# PAPR_STM32F030F4_V2.net
KiCad netlist of a schematic drawn in EasyEDA
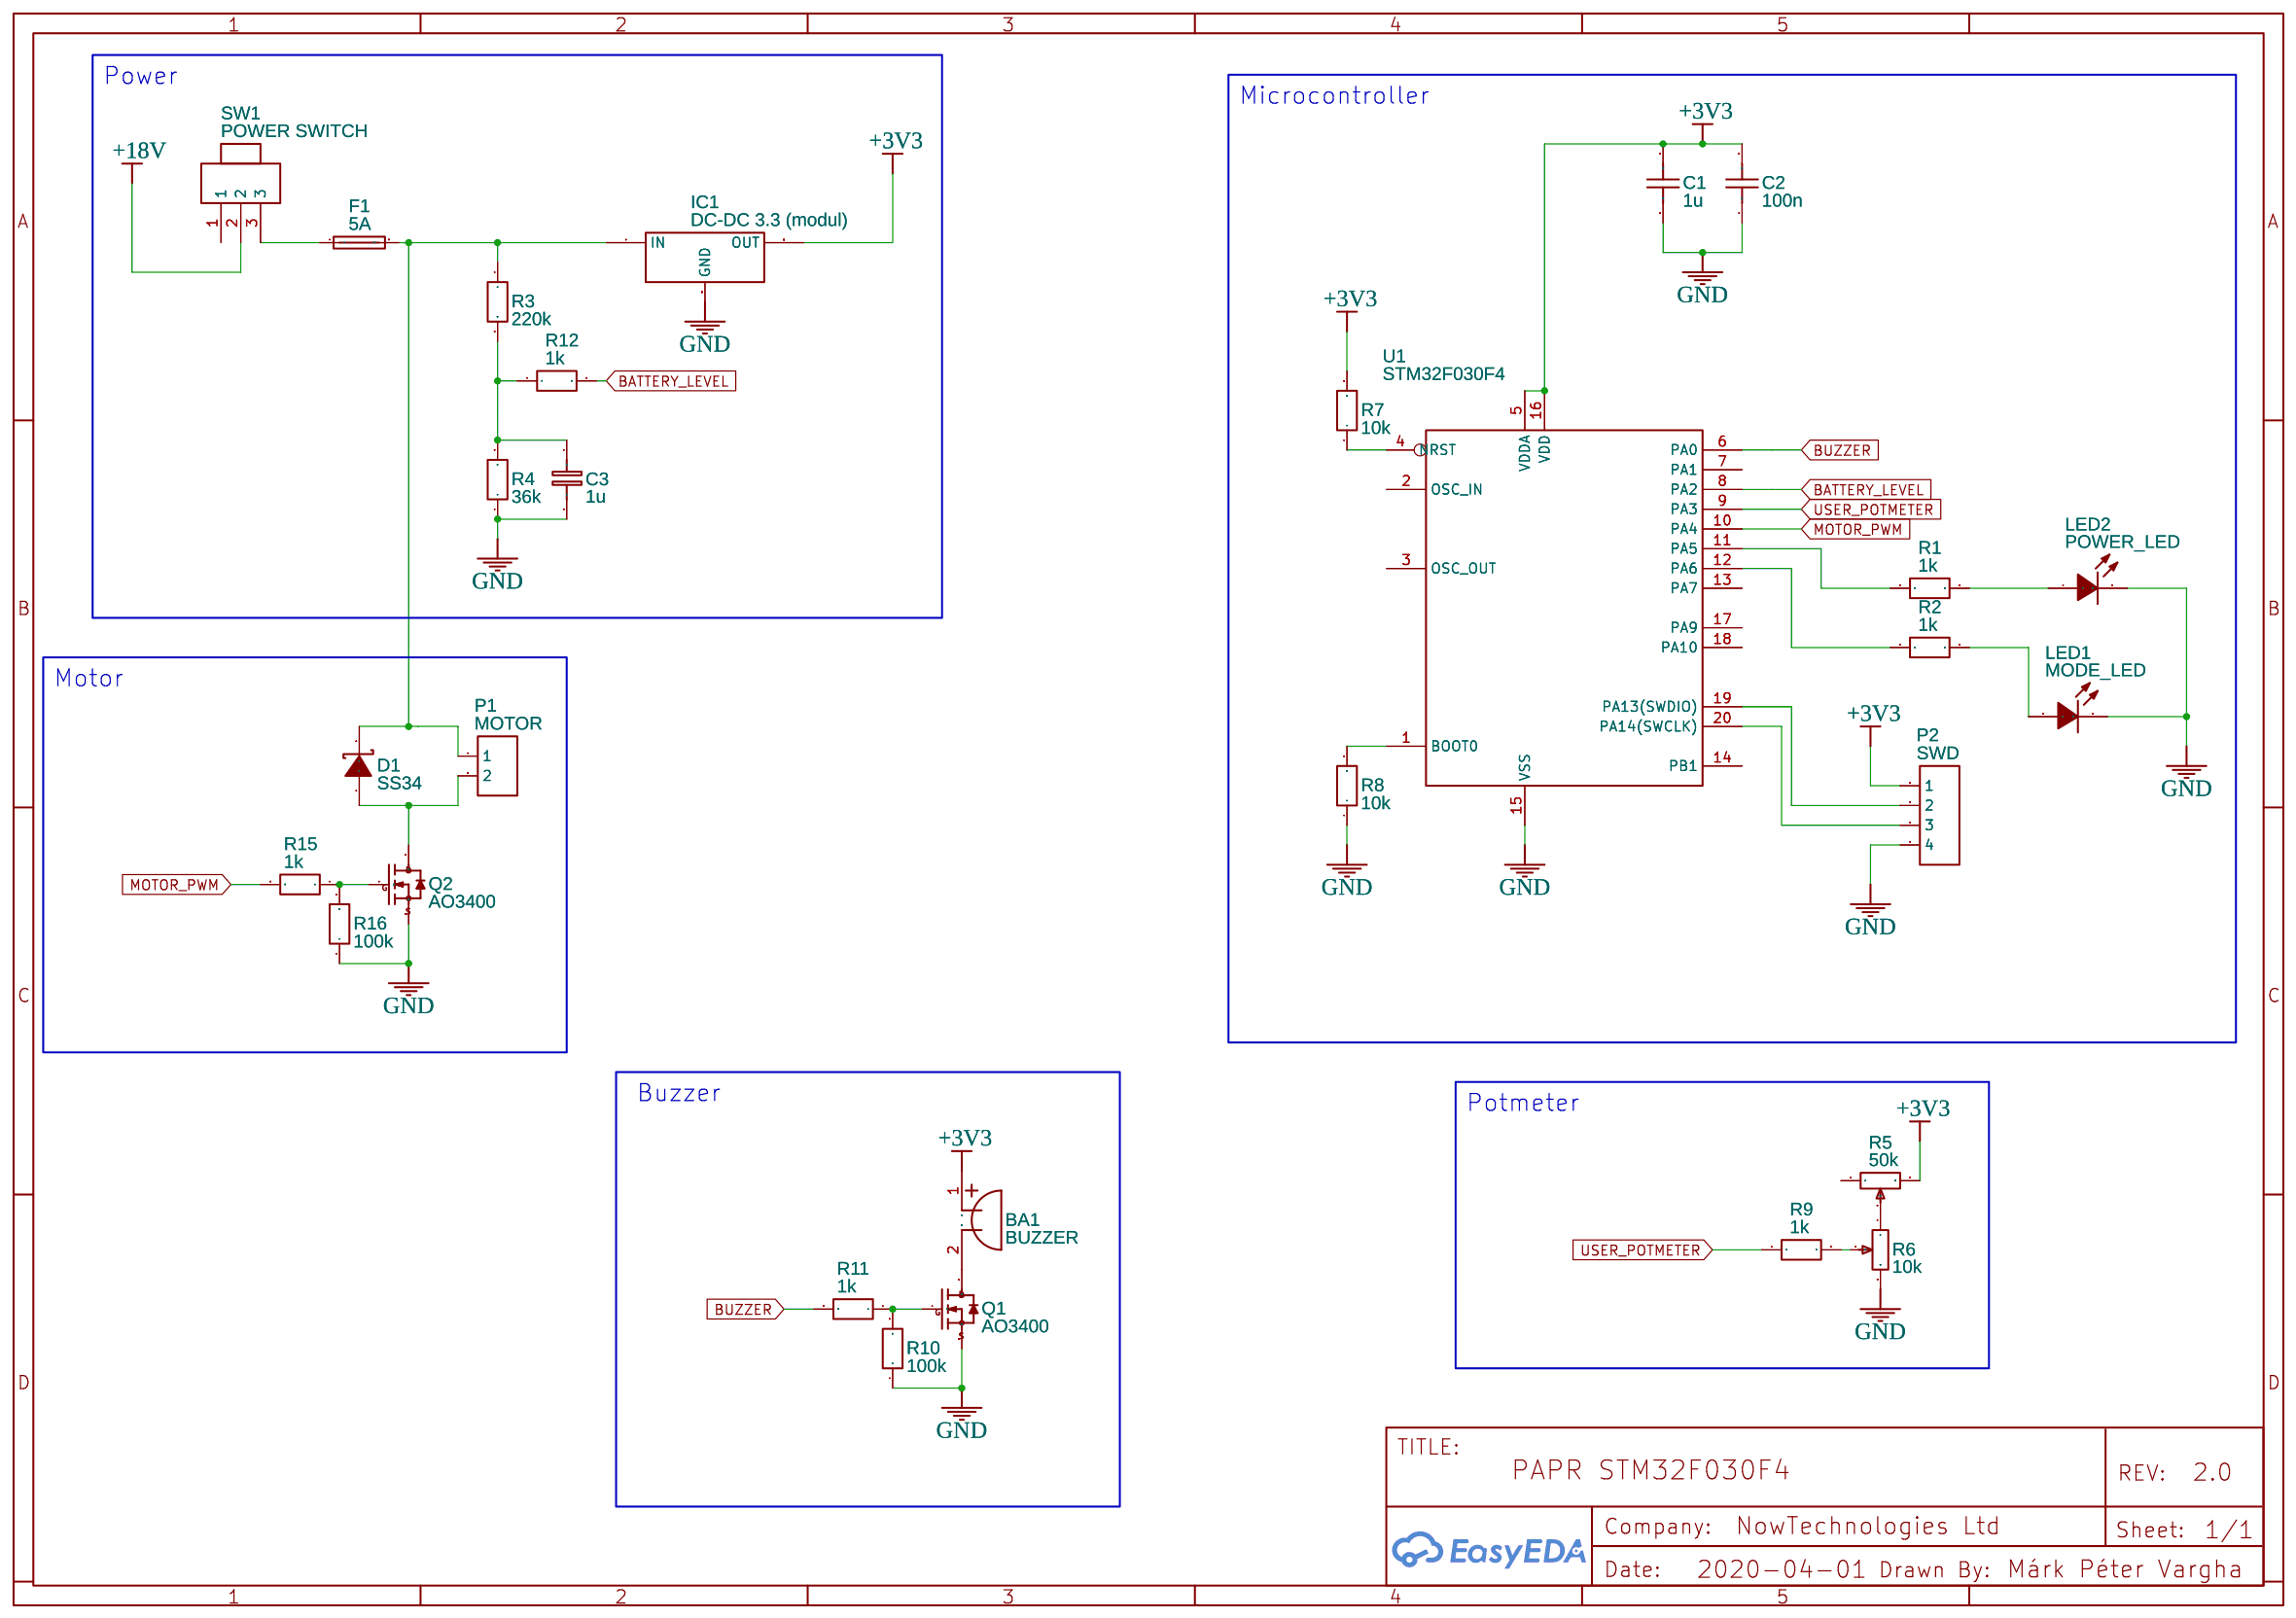
[diagram p0: schematic sheet]

(export (version "E")
  (design (tool "Eeschema 10.0.6"))
  (components
    (comp (ref "BA1") (value "BUZZER") (libsource (lib "") (part "9X5.5_BEEPER_5V")))
    (comp (ref "C1") (value "1u") (libsource (lib "") (part "Cap_RAD-0.1_US")))
    (comp (ref "C2") (value "100n") (libsource (lib "") (part "Cap_RAD-0.1_US")))
    (comp (ref "C3") (value "1u") (libsource (lib "") (part "Cap_RAD-0.1_EU")))
    (comp (ref "D1")
      (value "SS34")
      (fields (field (name "BOM_Supplier Part") "C13763"))
      (libsource (lib "") (part "SS34"))
    )
    (comp (ref "F1")
      (value "5A")
      (fields
        (field (name "BOM_Manufacturer Part") "5F 5A 250VACGlass tube fuse")
        (field (name "BOM_Supplier Part") "C3120")
      )
      (libsource (lib "") (part "5F 5A 250VACGlass tube fuse"))
    )
    (comp (ref "IC1") (value "DC-DC 3.3 (modul)") (libsource (lib "") (part "AMS1117 3.3")))
    (comp (ref "LED1")
      (value "MODE_LED")
      (fields
        (field (name "BOM_Manufacturer Part") "204-10SURD/S530-A3")
        (field (name "BOM_Supplier Part") "C99772")
      )
      (libsource (lib "") (part "204-10SURD/S530-A3"))
    )
    (comp (ref "LED2")
      (value "POWER_LED")
      (fields
        (field (name "BOM_Manufacturer Part") "204-10SURD/S530-A3")
        (field (name "BOM_Supplier Part") "C99772")
      )
      (libsource (lib "") (part "204-10SURD/S530-A3"))
    )
    (comp (ref "P1")
      (value "MOTOR")
      (fields
        (field (name "BOM_Manufacturer Part") "2.54-1*2PFemale")
        (field (name "BOM_Supplier Part") "C49661")
      )
      (libsource (lib "") (part "Header-Female-2.54_1x2"))
    )
    (comp (ref "P2") (value "SWD") (libsource (lib "") (part "4P")))
    (comp (ref "Q1")
      (value "AO3400")
      (fields (field (name "BOM_Supplier Part") "C122850"))
      (libsource (lib "") (part "AO3400_C122850"))
    )
    (comp (ref "Q2")
      (value "AO3400")
      (fields (field (name "BOM_Supplier Part") "C122850"))
      (libsource (lib "") (part "AO3400_C122850"))
    )
    (comp (ref "R1") (value "1k") (libsource (lib "") (part "Res_AXIAL-0.3(1/8W)_EU_1")))
    (comp (ref "R2") (value "1k") (libsource (lib "") (part "Res_AXIAL-0.3(1/8W)_EU_1")))
    (comp (ref "R3") (value "220k") (libsource (lib "") (part "Res_AXIAL-0.3(1/8W)_EU_2")))
    (comp (ref "R4") (value "36k") (libsource (lib "") (part "Res_AXIAL-0.3(1/8W)_EU")))
    (comp (ref "R5")
      (value "50k")
      (fields
        (field (name "BOM_Manufacturer Part") "3386P-1-101LF")
        (field (name "BOM_Supplier Part") "C125022")
      )
      (libsource (lib "") (part "potmeter"))
    )
    (comp (ref "R6")
      (value "10k")
      (fields
        (field (name "BOM_Manufacturer Part") "3386P-1-101LF")
        (field (name "BOM_Supplier Part") "C125022")
      )
      (libsource (lib "") (part "potmeter_1"))
    )
    (comp (ref "R7") (value "10k") (libsource (lib "") (part "Res_AXIAL-0.3(1/8W)_EU")))
    (comp (ref "R8") (value "10k") (libsource (lib "") (part "Res_AXIAL-0.3(1/8W)_EU")))
    (comp (ref "R9") (value "1k") (libsource (lib "") (part "Res_AXIAL-0.3(1/8W)_EU_1")))
    (comp (ref "R10") (value "100k") (libsource (lib "") (part "Res_AXIAL-0.3(1/8W)_EU")))
    (comp (ref "R11") (value "1k") (libsource (lib "") (part "Res_AXIAL-0.3(1/8W)_EU_3")))
    (comp (ref "R12") (value "1k") (libsource (lib "") (part "Res_AXIAL-0.3(1/8W)_EU_1")))
    (comp (ref "R15") (value "1k") (libsource (lib "") (part "Res_AXIAL-0.3(1/8W)_EU_3")))
    (comp (ref "R16") (value "100k") (libsource (lib "") (part "Res_AXIAL-0.3(1/8W)_EU")))
    (comp (ref "SW1")
      (value "POWER SWITCH")
      (fields
        (field (name "BOM_Manufacturer Part") "Rocker switch601-10211BB")
        (field (name "BOM_Supplier Part") "C67849")
      )
      (libsource (lib "") (part "Rocker switch601-10211BB"))
    )
    (comp (ref "U1") (value "STM32F030F4") (libsource (lib "") (part "STM32F030F4")))
  )
  (nets
    (net (code "1") (name "+3V3") (class "Default")
      (node (ref "BA1") (pin "1") (pinfunction "1_1") (pintype "unspecified"))
      (node (ref "C1") (pin "2") (pinfunction "2_2") (pintype "unspecified"))
      (node (ref "C2") (pin "2") (pinfunction "2_2") (pintype "unspecified"))
      (node (ref "IC1") (pin "OUT") (pinfunction "OUT_OUT") (pintype "unspecified"))
      (node (ref "P2") (pin "1") (pinfunction "1_1") (pintype "unspecified"))
      (node (ref "R5") (pin "3") (pinfunction "3_3") (pintype "input"))
      (node (ref "R7") (pin "2") (pinfunction "2_2") (pintype "unspecified"))
      (node (ref "U1") (pin "16") (pinfunction "VDD_16") (pintype "unspecified"))
      (node (ref "U1") (pin "5") (pinfunction "VDDA_5") (pintype "unspecified"))
    )
    (net (code "2") (name "+18V") (class "Default")
      (node (ref "SW1") (pin "2") (pinfunction "2_2") (pintype "unspecified"))
    )
    (net (code "3") (name "BATTERY_LEVEL") (class "Default")
      (node (ref "R12") (pin "2") (pinfunction "2_2") (pintype "unspecified"))
      (node (ref "U1") (pin "8") (pinfunction "PA2_8") (pintype "unspecified"))
    )
    (net (code "4") (name "BUZZER") (class "Default")
      (node (ref "R11") (pin "2") (pinfunction "2_2") (pintype "unspecified"))
      (node (ref "U1") (pin "6") (pinfunction "PA0_6") (pintype "unspecified"))
    )
    (net (code "5") (name "GND") (class "Default")
      (node (ref "C1") (pin "1") (pinfunction "1_1") (pintype "unspecified"))
      (node (ref "C2") (pin "1") (pinfunction "1_1") (pintype "unspecified"))
      (node (ref "C3") (pin "2") (pinfunction "2_2") (pintype "unspecified"))
      (node (ref "IC1") (pin "GND") (pinfunction "GND_GND") (pintype "input"))
      (node (ref "LED1") (pin "2") (pinfunction "K_2") (pintype "unspecified"))
      (node (ref "LED2") (pin "2") (pinfunction "K_2") (pintype "unspecified"))
      (node (ref "P2") (pin "4") (pinfunction "4_4") (pintype "unspecified"))
      (node (ref "Q1") (pin "2") (pinfunction "S_2") (pintype "unspecified"))
      (node (ref "Q2") (pin "2") (pinfunction "S_2") (pintype "unspecified"))
      (node (ref "R10") (pin "1") (pinfunction "1_1") (pintype "unspecified"))
      (node (ref "R16") (pin "1") (pinfunction "1_1") (pintype "unspecified"))
      (node (ref "R4") (pin "1") (pinfunction "1_1") (pintype "unspecified"))
      (node (ref "R6") (pin "3") (pinfunction "3_3") (pintype "input"))
      (node (ref "R8") (pin "1") (pinfunction "1_1") (pintype "unspecified"))
      (node (ref "U1") (pin "15") (pinfunction "VSS_15") (pintype "unspecified"))
    )
    (net (code "6") (name "MOTOR_PWM") (class "Default")
      (node (ref "R15") (pin "2") (pinfunction "2_2") (pintype "unspecified"))
      (node (ref "U1") (pin "10") (pinfunction "PA4_10") (pintype "unspecified"))
    )
    (net (code "7") (name "Net-(C3-Pad1)") (class "Default")
      (node (ref "C3") (pin "1") (pinfunction "1_1") (pintype "unspecified"))
      (node (ref "R12") (pin "1") (pinfunction "1_1") (pintype "unspecified"))
      (node (ref "R3") (pin "2") (pinfunction "2_2") (pintype "unspecified"))
      (node (ref "R4") (pin "2") (pinfunction "2_2") (pintype "unspecified"))
    )
    (net (code "8") (name "Net-(D1-A)") (class "Default")
      (node (ref "D1") (pin "1") (pinfunction "A_1") (pintype "unspecified"))
      (node (ref "P1") (pin "2") (pinfunction "2_2") (pintype "input"))
      (node (ref "Q2") (pin "3") (pinfunction "D_3") (pintype "unspecified"))
    )
    (net (code "9") (name "Net-(D1-K)") (class "Default")
      (node (ref "D1") (pin "2") (pinfunction "K_2") (pintype "unspecified"))
      (node (ref "F1") (pin "2") (pinfunction "2_2") (pintype "unspecified"))
      (node (ref "IC1") (pin "IN") (pinfunction "IN_IN") (pintype "input"))
      (node (ref "P1") (pin "1") (pinfunction "1_1") (pintype "input"))
      (node (ref "R3") (pin "1") (pinfunction "1_1") (pintype "unspecified"))
    )
    (net (code "10") (name "Net-(F1-Pad1)") (class "Default")
      (node (ref "F1") (pin "1") (pinfunction "1_1") (pintype "unspecified"))
      (node (ref "SW1") (pin "3") (pinfunction "3_3") (pintype "unspecified"))
    )
    (net (code "11") (name "Net-(LED1-A)") (class "Default")
      (node (ref "LED1") (pin "1") (pinfunction "A_1") (pintype "unspecified"))
      (node (ref "R2") (pin "2") (pinfunction "2_2") (pintype "unspecified"))
    )
    (net (code "12") (name "Net-(LED2-A)") (class "Default")
      (node (ref "LED2") (pin "1") (pinfunction "A_1") (pintype "unspecified"))
      (node (ref "R1") (pin "2") (pinfunction "2_2") (pintype "unspecified"))
    )
    (net (code "13") (name "Net-(Q1-D)") (class "Default")
      (node (ref "BA1") (pin "2") (pinfunction "2_2") (pintype "unspecified"))
      (node (ref "Q1") (pin "3") (pinfunction "D_3") (pintype "unspecified"))
    )
    (net (code "14") (name "Net-(Q1-G)") (class "Default")
      (node (ref "Q1") (pin "1") (pinfunction "G_1") (pintype "unspecified"))
      (node (ref "R10") (pin "2") (pinfunction "2_2") (pintype "unspecified"))
      (node (ref "R11") (pin "1") (pinfunction "1_1") (pintype "unspecified"))
    )
    (net (code "15") (name "Net-(Q2-G)") (class "Default")
      (node (ref "Q2") (pin "1") (pinfunction "G_1") (pintype "unspecified"))
      (node (ref "R15") (pin "1") (pinfunction "1_1") (pintype "unspecified"))
      (node (ref "R16") (pin "2") (pinfunction "2_2") (pintype "unspecified"))
    )
    (net (code "16") (name "Net-(R5-Pad2)") (class "Default")
      (node (ref "R5") (pin "2") (pinfunction "2_2") (pintype "input"))
      (node (ref "R6") (pin "1") (pinfunction "1_1") (pintype "input"))
    )
    (net (code "17") (name "Net-(R6-Pad2)") (class "Default")
      (node (ref "R6") (pin "2") (pinfunction "2_2") (pintype "input"))
      (node (ref "R9") (pin "2") (pinfunction "2_2") (pintype "unspecified"))
    )
    (net (code "18") (name "Net-(U1-BOOT0)") (class "Default")
      (node (ref "R8") (pin "2") (pinfunction "2_2") (pintype "unspecified"))
      (node (ref "U1") (pin "1") (pinfunction "BOOT0_1") (pintype "unspecified"))
    )
    (net (code "19") (name "Net-(U1-NRST)") (class "Default")
      (node (ref "R7") (pin "1") (pinfunction "1_1") (pintype "unspecified"))
      (node (ref "U1") (pin "4") (pinfunction "NRST_4") (pintype "unspecified"))
    )
    (net (code "20") (name "Net-(U1-PA5)") (class "Default")
      (node (ref "R1") (pin "1") (pinfunction "1_1") (pintype "unspecified"))
      (node (ref "U1") (pin "11") (pinfunction "PA5_11") (pintype "unspecified"))
    )
    (net (code "21") (name "Net-(U1-PA6)") (class "Default")
      (node (ref "R2") (pin "1") (pinfunction "1_1") (pintype "unspecified"))
      (node (ref "U1") (pin "12") (pinfunction "PA6_12") (pintype "unspecified"))
    )
    (net (code "22") (name "Net-(U1-PA13(SWDIO))") (class "Default")
      (node (ref "P2") (pin "2") (pinfunction "2_2") (pintype "unspecified"))
      (node (ref "U1") (pin "19") (pinfunction "PA13(SWDIO)_19") (pintype "unspecified"))
    )
    (net (code "23") (name "Net-(U1-PA14(SWCLK))") (class "Default")
      (node (ref "P2") (pin "3") (pinfunction "3_3") (pintype "unspecified"))
      (node (ref "U1") (pin "20") (pinfunction "PA14(SWCLK)_20") (pintype "unspecified"))
    )
    (net (code "24") (name "USER_POTMETER") (class "Default")
      (node (ref "R9") (pin "1") (pinfunction "1_1") (pintype "unspecified"))
      (node (ref "U1") (pin "9") (pinfunction "PA3_9") (pintype "unspecified"))
    )
    (net (code "25") (name "unconnected-(R5-Pad1)") (class "Default")
      (node (ref "R5") (pin "1") (pinfunction "1_1") (pintype "input"))
    )
    (net (code "26") (name "unconnected-(SW1-Pad1)") (class "Default")
      (node (ref "SW1") (pin "1") (pinfunction "1_1") (pintype "unspecified"))
    )
    (net (code "27") (name "unconnected-(U1-OSC_IN-Pad2)") (class "Default")
      (node (ref "U1") (pin "2") (pinfunction "OSC_IN_2") (pintype "unspecified"))
    )
    (net (code "28") (name "unconnected-(U1-OSC_OUT-Pad3)") (class "Default")
      (node (ref "U1") (pin "3") (pinfunction "OSC_OUT_3") (pintype "unspecified"))
    )
    (net (code "29") (name "unconnected-(U1-PA1-Pad7)") (class "Default")
      (node (ref "U1") (pin "7") (pinfunction "PA1_7") (pintype "unspecified"))
    )
    (net (code "30") (name "unconnected-(U1-PA7-Pad13)") (class "Default")
      (node (ref "U1") (pin "13") (pinfunction "PA7_13") (pintype "unspecified"))
    )
    (net (code "31") (name "unconnected-(U1-PA9-Pad17)") (class "Default")
      (node (ref "U1") (pin "17") (pinfunction "PA9_17") (pintype "unspecified"))
    )
    (net (code "32") (name "unconnected-(U1-PA10-Pad18)") (class "Default")
      (node (ref "U1") (pin "18") (pinfunction "PA10_18") (pintype "unspecified"))
    )
    (net (code "33") (name "unconnected-(U1-PB1-Pad14)") (class "Default")
      (node (ref "U1") (pin "14") (pinfunction "PB1_14") (pintype "unspecified"))
    )
  )
)
